# uuni.net
KiCad netlist of a schematic drawn in EAGLE
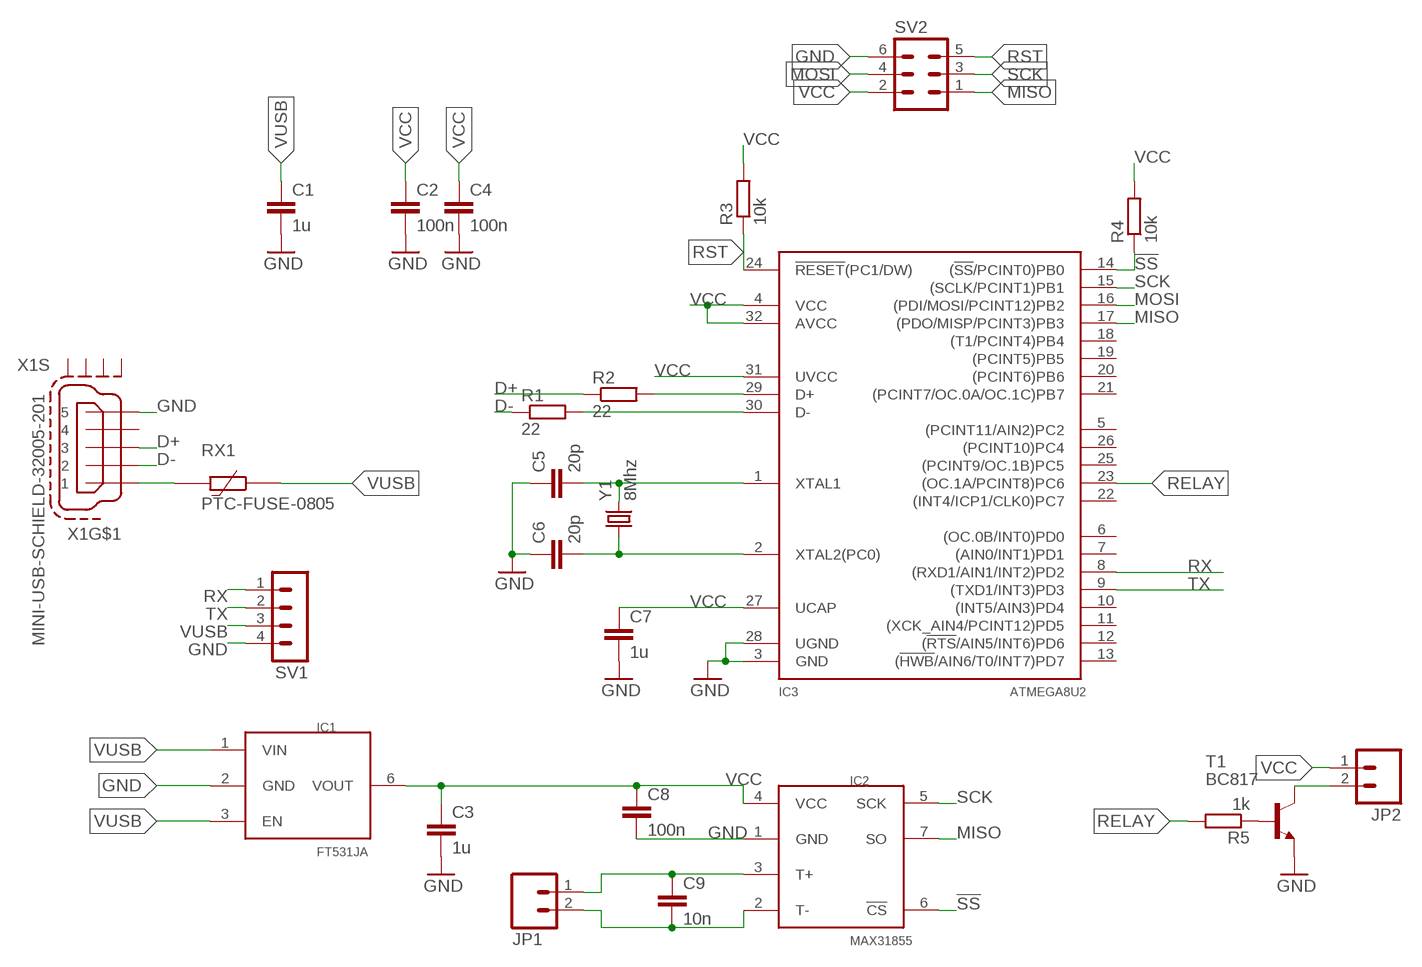
[diagram p0: schematic, sheet 1]

(export (version "E")
  (design (tool "Eeschema 10.0.6"))
  (components
    (comp (ref "C1")
      (value "1u")
      (footprint "eagle-import:C0603")
      (libsource (lib "eagle-import") (part "C-EUC0603"))
    )
    (comp (ref "C2")
      (value "100n")
      (footprint "eagle-import:C0603")
      (libsource (lib "eagle-import") (part "C-EUC0603"))
    )
    (comp (ref "C3")
      (value "1u")
      (footprint "eagle-import:C0603")
      (libsource (lib "eagle-import") (part "C-EUC0603"))
    )
    (comp (ref "C4")
      (value "100n")
      (footprint "eagle-import:C0603")
      (libsource (lib "eagle-import") (part "C-EUC0603"))
    )
    (comp (ref "C5")
      (value "20p")
      (footprint "eagle-import:C0603")
      (libsource (lib "eagle-import") (part "C-EUC0603"))
    )
    (comp (ref "C6")
      (value "20p")
      (footprint "eagle-import:C0603")
      (libsource (lib "eagle-import") (part "C-EUC0603"))
    )
    (comp (ref "C7")
      (value "1u")
      (footprint "eagle-import:C0603")
      (libsource (lib "eagle-import") (part "C-EUC0603"))
    )
    (comp (ref "C8")
      (value "100n")
      (footprint "eagle-import:C0603")
      (libsource (lib "eagle-import") (part "C-EUC0603"))
    )
    (comp (ref "C9")
      (value "10n")
      (footprint "eagle-import:C0603")
      (libsource (lib "eagle-import") (part "C-EUC0603"))
    )
    (comp (ref "IC1")
      (value "FT531JA")
      (footprint "eagle-import:SC-74")
      (libsource (lib "eagle-import") (part "FT531JA"))
    )
    (comp (ref "IC2")
      (value "MAX31855")
      (footprint "eagle-import:SO8")
      (libsource (lib "eagle-import") (part "MAX31855"))
    )
    (comp (ref "IC3")
      (value "ATMEGA8U2")
      (footprint "eagle-import:TQFP32-08")
      (libsource (lib "eagle-import") (part "ATMEGA8U2"))
    )
    (comp (ref "JP1")
      (value "M025MM")
      (footprint "eagle-import:SCREWTERMINAL-5MM-2")
      (libsource (lib "eagle-import") (part "M025MM"))
    )
    (comp (ref "JP2")
      (value "M02LOCK")
      (footprint "eagle-import:1X02_LOCK")
      (libsource (lib "eagle-import") (part "M02LOCK"))
    )
    (comp (ref "R1")
      (value "22")
      (footprint "eagle-import:R0603")
      (libsource (lib "eagle-import") (part "R-EU_R0603"))
    )
    (comp (ref "R2")
      (value "22")
      (footprint "eagle-import:R0603")
      (libsource (lib "eagle-import") (part "R-EU_R0603"))
    )
    (comp (ref "R3")
      (value "10k")
      (footprint "eagle-import:R0603")
      (libsource (lib "eagle-import") (part "R-EU_R0603"))
    )
    (comp (ref "R4")
      (value "10k")
      (footprint "eagle-import:R0603")
      (libsource (lib "eagle-import") (part "R-EU_R0603"))
    )
    (comp (ref "R5")
      (value "1k")
      (footprint "eagle-import:R0603")
      (libsource (lib "eagle-import") (part "R-EU_R0603"))
    )
    (comp (ref "RX1")
      (value "PTC-FUSE-0805")
      (footprint "eagle-import:R0805")
      (libsource (lib "eagle-import") (part "PTC-FUSE-0805"))
    )
    (comp (ref "SV1")
      (value "MA04-1")
      (footprint "eagle-import:MA04-1")
      (libsource (lib "eagle-import") (part "MA04-1"))
    )
    (comp (ref "SV2")
      (value "MA03-2")
      (footprint "eagle-import:MA03-2")
      (libsource (lib "eagle-import") (part "MA03-2"))
    )
    (comp (ref "T1")
      (value "BC817")
      (footprint "eagle-import:SOT23-BEC")
      (libsource (lib "eagle-import") (part "-NPN-SOT23-BECBC817-40"))
    )
    (comp (ref "X1")
      (value "MINI-USB-SCHIELD-32005-201")
      (footprint "eagle-import:32005-201")
      (libsource (lib "eagle-import") (part "MINI-USB-SCHIELD-32005-201"))
    )
    (comp (ref "Y1")
      (value "8Mhz")
      (footprint "eagle-import:HC49UP")
      (libsource (lib "eagle-import") (part "CRYSTALSMD"))
    )
  )
  (nets
    (net (code "1") (name "/D+") (class "Default")
      (node (ref "R2") (pin "1") (pinfunction "1_1") (pintype "passive"))
      (node (ref "X1") (pin "3") (pinfunction "3_3") (pintype "passive"))
    )
    (net (code "2") (name "/D-") (class "Default")
      (node (ref "R1") (pin "1") (pinfunction "1_1") (pintype "passive"))
      (node (ref "X1") (pin "2") (pinfunction "2_2") (pintype "passive"))
    )
    (net (code "3") (name "/RX") (class "Default")
      (node (ref "IC3") (pin "8") (pinfunction "(RXD1/AIN1/INT2)PD2_8") (pintype "bidirectional"))
      (node (ref "SV1") (pin "1") (pinfunction "1_1") (pintype "passive"))
    )
    (net (code "4") (name "/TX") (class "Default")
      (node (ref "IC3") (pin "9") (pinfunction "(TXD1/INT3)PD3_9") (pintype "bidirectional"))
      (node (ref "SV1") (pin "2") (pinfunction "2_2") (pintype "passive"))
    )
    (net (code "5") (name "/~{SS}") (class "Default")
      (node (ref "IC2") (pin "6") (pinfunction "~{CS}_6") (pintype "bidirectional"))
      (node (ref "IC3") (pin "14") (pinfunction "(~{SS}/PCINT0)PB0_14") (pintype "bidirectional"))
      (node (ref "R4") (pin "1") (pinfunction "1_1") (pintype "passive"))
    )
    (net (code "6") (name "GND") (class "Default")
      (node (ref "C1") (pin "2") (pinfunction "2_2") (pintype "passive"))
      (node (ref "C2") (pin "2") (pinfunction "2_2") (pintype "passive"))
      (node (ref "C3") (pin "2") (pinfunction "2_2") (pintype "passive"))
      (node (ref "C4") (pin "2") (pinfunction "2_2") (pintype "passive"))
      (node (ref "C5") (pin "1") (pinfunction "1_1") (pintype "passive"))
      (node (ref "C6") (pin "1") (pinfunction "1_1") (pintype "passive"))
      (node (ref "C7") (pin "2") (pinfunction "2_2") (pintype "passive"))
      (node (ref "C8") (pin "2") (pinfunction "2_2") (pintype "passive"))
      (node (ref "IC1") (pin "2") (pinfunction "GND_2") (pintype "bidirectional"))
      (node (ref "IC2") (pin "1") (pinfunction "GND_1") (pintype "bidirectional"))
      (node (ref "IC3") (pin "28") (pinfunction "UGND_28") (pintype "bidirectional"))
      (node (ref "IC3") (pin "3") (pinfunction "GND_3") (pintype "bidirectional"))
      (node (ref "SV1") (pin "4") (pinfunction "4_4") (pintype "passive"))
      (node (ref "SV2") (pin "6") (pinfunction "6_6") (pintype "passive"))
      (node (ref "T1") (pin "E") (pinfunction "E_E") (pintype "passive"))
      (node (ref "X1") (pin "5") (pinfunction "5_5") (pintype "passive"))
    )
    (net (code "7") (name "MISO") (class "Default")
      (node (ref "IC2") (pin "7") (pinfunction "SO_7") (pintype "bidirectional"))
      (node (ref "IC3") (pin "17") (pinfunction "(PDO/MISP/PCINT3)PB3_17") (pintype "bidirectional"))
      (node (ref "SV2") (pin "1") (pinfunction "1_1") (pintype "passive"))
    )
    (net (code "8") (name "MOSI") (class "Default")
      (node (ref "IC3") (pin "16") (pinfunction "(PDI/MOSI/PCINT12)PB2_16") (pintype "bidirectional"))
      (node (ref "SV2") (pin "4") (pinfunction "4_4") (pintype "passive"))
    )
    (net (code "9") (name "Net-(IC2-T+)") (class "Default")
      (node (ref "C9") (pin "1") (pinfunction "1_1") (pintype "passive"))
      (node (ref "IC2") (pin "3") (pinfunction "T+_3") (pintype "bidirectional"))
      (node (ref "JP1") (pin "1") (pinfunction "1_1") (pintype "passive"))
    )
    (net (code "10") (name "Net-(IC2-T-)") (class "Default")
      (node (ref "C9") (pin "2") (pinfunction "2_2") (pintype "passive"))
      (node (ref "IC2") (pin "2") (pinfunction "T-_2") (pintype "bidirectional"))
      (node (ref "JP1") (pin "2") (pinfunction "2_2") (pintype "passive"))
    )
    (net (code "11") (name "Net-(IC3-D+)") (class "Default")
      (node (ref "IC3") (pin "29") (pinfunction "D+_29") (pintype "bidirectional"))
      (node (ref "R2") (pin "2") (pinfunction "2_2") (pintype "passive"))
    )
    (net (code "12") (name "Net-(IC3-D-)") (class "Default")
      (node (ref "IC3") (pin "30") (pinfunction "D-_30") (pintype "bidirectional"))
      (node (ref "R1") (pin "2") (pinfunction "2_2") (pintype "passive"))
    )
    (net (code "13") (name "Net-(IC3-XTAL1)") (class "Default")
      (node (ref "C5") (pin "2") (pinfunction "2_2") (pintype "passive"))
      (node (ref "IC3") (pin "1") (pinfunction "XTAL1_1") (pintype "bidirectional"))
      (node (ref "Y1") (pin "2") (pinfunction "2_2") (pintype "passive"))
    )
    (net (code "14") (name "Net-(IC3-XTAL2(PC0))") (class "Default")
      (node (ref "C6") (pin "2") (pinfunction "2_2") (pintype "passive"))
      (node (ref "IC3") (pin "2") (pinfunction "XTAL2(PC0)_2") (pintype "bidirectional"))
      (node (ref "Y1") (pin "1") (pinfunction "1_1") (pintype "passive"))
    )
    (net (code "15") (name "Net-(JP2-Pad2)") (class "Default")
      (node (ref "JP2") (pin "2") (pinfunction "2_2") (pintype "passive"))
      (node (ref "T1") (pin "C") (pinfunction "C_C") (pintype "passive"))
    )
    (net (code "16") (name "Net-(R5-Pad1)") (class "Default")
      (node (ref "R5") (pin "1") (pinfunction "1_1") (pintype "passive"))
      (node (ref "T1") (pin "B") (pinfunction "B_B") (pintype "passive"))
    )
    (net (code "17") (name "Net-(RX1-P$1)") (class "Default")
      (node (ref "RX1") (pin "1") (pinfunction "P$1_1") (pintype "bidirectional"))
      (node (ref "X1") (pin "1") (pinfunction "1_1") (pintype "passive"))
    )
    (net (code "18") (name "RELAY") (class "Default")
      (node (ref "IC3") (pin "23") (pinfunction "(OC.1A/PCINT8)PC6_23") (pintype "bidirectional"))
      (node (ref "R5") (pin "2") (pinfunction "2_2") (pintype "passive"))
    )
    (net (code "19") (name "RST") (class "Default")
      (node (ref "IC3") (pin "24") (pinfunction "~{RESET}(PC1/DW)_24") (pintype "bidirectional"))
      (node (ref "R3") (pin "1") (pinfunction "1_1") (pintype "passive"))
      (node (ref "SV2") (pin "5") (pinfunction "5_5") (pintype "passive"))
    )
    (net (code "20") (name "SCK") (class "Default")
      (node (ref "IC2") (pin "5") (pinfunction "SCK_5") (pintype "bidirectional"))
      (node (ref "IC3") (pin "15") (pinfunction "(SCLK/PCINT1)PB1_15") (pintype "bidirectional"))
      (node (ref "SV2") (pin "3") (pinfunction "3_3") (pintype "passive"))
    )
    (net (code "21") (name "VCC") (class "Default")
      (node (ref "C2") (pin "1") (pinfunction "1_1") (pintype "passive"))
      (node (ref "C3") (pin "1") (pinfunction "1_1") (pintype "passive"))
      (node (ref "C4") (pin "1") (pinfunction "1_1") (pintype "passive"))
      (node (ref "C7") (pin "1") (pinfunction "1_1") (pintype "passive"))
      (node (ref "C8") (pin "1") (pinfunction "1_1") (pintype "passive"))
      (node (ref "IC1") (pin "6") (pinfunction "VOUT_6") (pintype "bidirectional"))
      (node (ref "IC2") (pin "4") (pinfunction "VCC_4") (pintype "bidirectional"))
      (node (ref "IC3") (pin "27") (pinfunction "UCAP_27") (pintype "bidirectional"))
      (node (ref "IC3") (pin "31") (pinfunction "UVCC_31") (pintype "bidirectional"))
      (node (ref "IC3") (pin "32") (pinfunction "AVCC_32") (pintype "bidirectional"))
      (node (ref "IC3") (pin "4") (pinfunction "VCC_4") (pintype "bidirectional"))
      (node (ref "JP2") (pin "1") (pinfunction "1_1") (pintype "passive"))
      (node (ref "R3") (pin "2") (pinfunction "2_2") (pintype "passive"))
      (node (ref "R4") (pin "2") (pinfunction "2_2") (pintype "passive"))
      (node (ref "SV2") (pin "2") (pinfunction "2_2") (pintype "passive"))
    )
    (net (code "22") (name "VUSB") (class "Default")
      (node (ref "C1") (pin "1") (pinfunction "1_1") (pintype "passive"))
      (node (ref "IC1") (pin "1") (pinfunction "VIN_1") (pintype "bidirectional"))
      (node (ref "IC1") (pin "3") (pinfunction "EN_3") (pintype "bidirectional"))
      (node (ref "RX1") (pin "2") (pinfunction "P$2_2") (pintype "bidirectional"))
      (node (ref "SV1") (pin "3") (pinfunction "3_3") (pintype "passive"))
    )
    (net (code "23") (name "unconnected-(IC3-(AIN0{slash}INT1)PD1-Pad7)") (class "Default")
      (node (ref "IC3") (pin "7") (pinfunction "(AIN0/INT1)PD1_7") (pintype "bidirectional"))
    )
    (net (code "24") (name "unconnected-(IC3-(INT4{slash}ICP1{slash}CLK0)PC7-Pad22)") (class "Default")
      (node (ref "IC3") (pin "22") (pinfunction "(INT4/ICP1/CLK0)PC7_22") (pintype "bidirectional"))
    )
    (net (code "25") (name "unconnected-(IC3-(INT5{slash}AIN3)PD4-Pad10)") (class "Default")
      (node (ref "IC3") (pin "10") (pinfunction "(INT5/AIN3)PD4_10") (pintype "bidirectional"))
    )
    (net (code "26") (name "unconnected-(IC3-(OC.0B{slash}INT0)PD0-Pad6)") (class "Default")
      (node (ref "IC3") (pin "6") (pinfunction "(OC.0B/INT0)PD0_6") (pintype "bidirectional"))
    )
    (net (code "27") (name "unconnected-(IC3-(PCINT5)PB5-Pad19)") (class "Default")
      (node (ref "IC3") (pin "19") (pinfunction "(PCINT5)PB5_19") (pintype "bidirectional"))
    )
    (net (code "28") (name "unconnected-(IC3-(PCINT6)PB6-Pad20)") (class "Default")
      (node (ref "IC3") (pin "20") (pinfunction "(PCINT6)PB6_20") (pintype "bidirectional"))
    )
    (net (code "29") (name "unconnected-(IC3-(PCINT7{slash}OC.0A{slash}OC.1C)PB7-Pad21)") (class "Default")
      (node (ref "IC3") (pin "21") (pinfunction "(PCINT7/OC.0A/OC.1C)PB7_21") (pintype "bidirectional"))
    )
    (net (code "30") (name "unconnected-(IC3-(PCINT9{slash}OC.1B)PC5-Pad25)") (class "Default")
      (node (ref "IC3") (pin "25") (pinfunction "(PCINT9/OC.1B)PC5_25") (pintype "bidirectional"))
    )
    (net (code "31") (name "unconnected-(IC3-(PCINT10)PC4-Pad26)") (class "Default")
      (node (ref "IC3") (pin "26") (pinfunction "(PCINT10)PC4_26") (pintype "bidirectional"))
    )
    (net (code "32") (name "unconnected-(IC3-(PCINT11{slash}AIN2)PC2-Pad5)") (class "Default")
      (node (ref "IC3") (pin "5") (pinfunction "(PCINT11/AIN2)PC2_5") (pintype "bidirectional"))
    )
    (net (code "33") (name "unconnected-(IC3-(T1{slash}PCINT4)PB4-Pad18)") (class "Default")
      (node (ref "IC3") (pin "18") (pinfunction "(T1/PCINT4)PB4_18") (pintype "bidirectional"))
    )
    (net (code "34") (name "unconnected-(IC3-(XCK_AIN4{slash}PCINT12)PD5-Pad11)") (class "Default")
      (node (ref "IC3") (pin "11") (pinfunction "(XCK_AIN4/PCINT12)PD5_11") (pintype "bidirectional"))
    )
    (net (code "35") (name "unconnected-(IC3-(~{HWB}{slash}AIN6{slash}T0{slash}INT7)PD7-Pad13)") (class "Default")
      (node (ref "IC3") (pin "13") (pinfunction "(~{HWB}/AIN6/T0/INT7)PD7_13") (pintype "bidirectional"))
    )
    (net (code "36") (name "unconnected-(IC3-(~{RTS}{slash}AIN5{slash}INT6)PD6-Pad12)") (class "Default")
      (node (ref "IC3") (pin "12") (pinfunction "(~{RTS}/AIN5/INT6)PD6_12") (pintype "bidirectional"))
    )
    (net (code "37") (name "unconnected-(X1-Pad4)") (class "Default")
      (node (ref "X1") (pin "4") (pinfunction "4_4") (pintype "passive"))
    )
    (net (code "38") (name "unconnected-(X1B-S1-PadM1)") (class "Default")
      (node (ref "X1") (pin "M1") (pinfunction "S1_M1") (pintype "passive"))
    )
    (net (code "39") (name "unconnected-(X1B-S2-PadM2)") (class "Default")
      (node (ref "X1") (pin "M2") (pinfunction "S2_M2") (pintype "passive"))
    )
    (net (code "40") (name "unconnected-(X1B-S3-PadM3)") (class "Default")
      (node (ref "X1") (pin "M3") (pinfunction "S3_M3") (pintype "passive"))
    )
    (net (code "41") (name "unconnected-(X1B-S4-PadM4)") (class "Default")
      (node (ref "X1") (pin "M4") (pinfunction "S4_M4") (pintype "passive"))
    )
  )
)
